# APDS-9301_Breakout.net
KiCad netlist of a schematic drawn in EAGLE
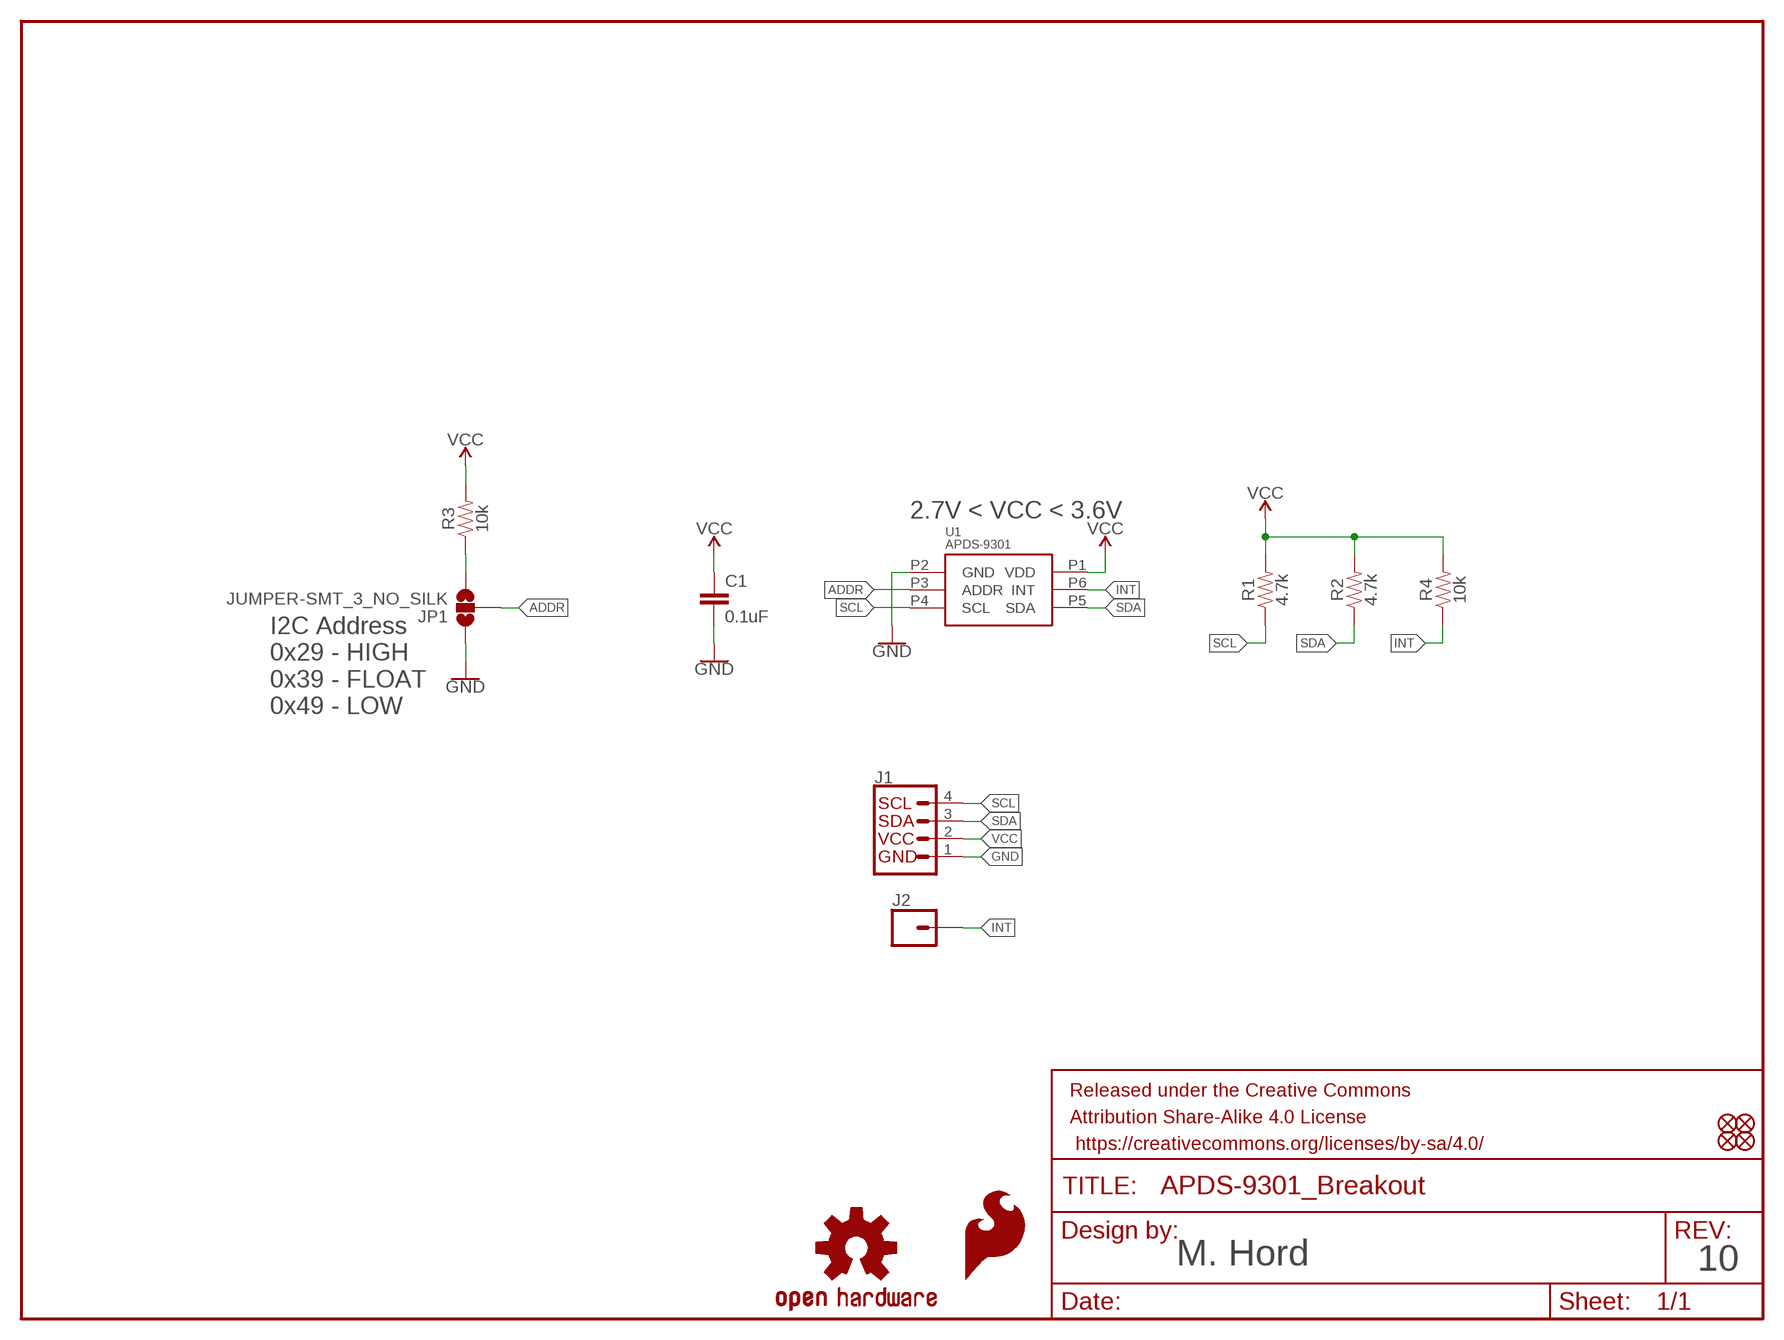
[diagram p0: schematic, sheet 1]

(export (version "E")
  (design (tool "Eeschema 10.0.6"))
  (components
    (comp (ref "C1")
      (value "0.1uF")
      (footprint "eagle-import:0603")
      (libsource (lib "eagle-import") (part "0.1UF-0603-25V-5%"))
    )
    (comp (ref "FD1")
      (value "FIDUCIALUFIDUCIAL")
      (footprint "eagle-import:FIDUCIAL-MICRO")
      (libsource (lib "eagle-import") (part "FIDUCIALUFIDUCIAL"))
    )
    (comp (ref "FD2")
      (value "FIDUCIALUFIDUCIAL")
      (footprint "eagle-import:FIDUCIAL-MICRO")
      (libsource (lib "eagle-import") (part "FIDUCIALUFIDUCIAL"))
    )
    (comp (ref "FD3")
      (value "FIDUCIALUFIDUCIAL")
      (footprint "eagle-import:FIDUCIAL-MICRO")
      (libsource (lib "eagle-import") (part "FIDUCIALUFIDUCIAL"))
    )
    (comp (ref "FD4")
      (value "FIDUCIALUFIDUCIAL")
      (footprint "eagle-import:FIDUCIAL-MICRO")
      (libsource (lib "eagle-import") (part "FIDUCIALUFIDUCIAL"))
    )
    (comp (ref "FRAME1")
      (value "FRAME-LETTER")
      (footprint "eagle-import:CREATIVE_COMMONS")
      (libsource (lib "eagle-import") (part "FRAME-LETTER"))
    )
    (comp (ref "J1")
      (value "I2C_STANDARD")
      (footprint "eagle-import:1X04")
      (libsource (lib "eagle-import") (part "I2C_STANDARD"))
    )
    (comp (ref "J2")
      (value "CONN_01")
      (footprint "eagle-import:1X01")
      (libsource (lib "eagle-import") (part "CONN_01"))
    )
    (comp (ref "JP1")
      (value "JUMPER-SMT_3_NO_SILK")
      (footprint "eagle-import:SMT-JUMPER_3_NO_SILK")
      (libsource (lib "eagle-import") (part "JUMPER-SMT_3_NO_SILK"))
    )
    (comp (ref "LOGO1")
      (value "SFE_LOGO_FLAME.1_INCH")
      (footprint "eagle-import:SFE_LOGO_FLAME_.1")
      (libsource (lib "eagle-import") (part "SFE_LOGO_FLAME.1_INCH"))
    )
    (comp (ref "LOGO2")
      (value "OSHW-LOGOS")
      (footprint "eagle-import:OSHW-LOGO-S")
      (libsource (lib "eagle-import") (part "OSHW-LOGOS"))
    )
    (comp (ref "R1")
      (value "4.7k")
      (footprint "eagle-import:0603")
      (libsource (lib "eagle-import") (part "4.7KOHM-0603-1/10W-1%"))
    )
    (comp (ref "R2")
      (value "4.7k")
      (footprint "eagle-import:0603")
      (libsource (lib "eagle-import") (part "4.7KOHM-0603-1/10W-1%"))
    )
    (comp (ref "R3")
      (value "10k")
      (footprint "eagle-import:0603")
      (libsource (lib "eagle-import") (part "10KOHM-0603-1/10W-1%"))
    )
    (comp (ref "R4")
      (value "10k")
      (footprint "eagle-import:0603")
      (libsource (lib "eagle-import") (part "10KOHM-0603-1/10W-1%"))
    )
    (comp (ref "U1")
      (value "APDS-9301")
      (footprint "eagle-import:CHIPLED-6")
      (libsource (lib "eagle-import") (part "APDS-9301"))
    )
  )
  (nets
    (net (code "1") (name "ADDR") (class "Default")
      (node (ref "JP1") (pin "2") (pinfunction "2_2") (pintype "passive"))
      (node (ref "U1") (pin "P3") (pinfunction "ADDR_P3") (pintype "bidirectional"))
    )
    (net (code "2") (name "GND") (class "Default")
      (node (ref "C1") (pin "2") (pinfunction "2_2") (pintype "passive"))
      (node (ref "J1") (pin "1") (pinfunction "1_1") (pintype "power_in"))
      (node (ref "JP1") (pin "1") (pinfunction "1_1") (pintype "passive"))
      (node (ref "U1") (pin "P2") (pinfunction "GND_P2") (pintype "bidirectional"))
    )
    (net (code "3") (name "INT") (class "Default")
      (node (ref "J2") (pin "1") (pinfunction "1_1") (pintype "passive"))
      (node (ref "R4") (pin "1") (pinfunction "1_1") (pintype "passive"))
      (node (ref "U1") (pin "P6") (pinfunction "INT_P6") (pintype "bidirectional"))
    )
    (net (code "4") (name "Net-(JP1-Pad3)") (class "Default")
      (node (ref "JP1") (pin "3") (pinfunction "3_3") (pintype "passive"))
      (node (ref "R3") (pin "1") (pinfunction "1_1") (pintype "passive"))
    )
    (net (code "5") (name "SCL") (class "Default")
      (node (ref "J1") (pin "4") (pinfunction "4_4") (pintype "passive"))
      (node (ref "R1") (pin "1") (pinfunction "1_1") (pintype "passive"))
      (node (ref "U1") (pin "P4") (pinfunction "SCL_P4") (pintype "bidirectional"))
    )
    (net (code "6") (name "SDA") (class "Default")
      (node (ref "J1") (pin "3") (pinfunction "3_3") (pintype "passive"))
      (node (ref "R2") (pin "1") (pinfunction "1_1") (pintype "passive"))
      (node (ref "U1") (pin "P5") (pinfunction "SDA_P5") (pintype "bidirectional"))
    )
    (net (code "7") (name "VCC") (class "Default")
      (node (ref "C1") (pin "1") (pinfunction "1_1") (pintype "passive"))
      (node (ref "J1") (pin "2") (pinfunction "2_2") (pintype "power_in"))
      (node (ref "R1") (pin "2") (pinfunction "2_2") (pintype "passive"))
      (node (ref "R2") (pin "2") (pinfunction "2_2") (pintype "passive"))
      (node (ref "R3") (pin "2") (pinfunction "2_2") (pintype "passive"))
      (node (ref "R4") (pin "2") (pinfunction "2_2") (pintype "passive"))
      (node (ref "U1") (pin "P1") (pinfunction "VDD_P1") (pintype "bidirectional"))
    )
  )
)
